# SHEET1.net
KiCad netlist of a schematic drawn in Altium Designer
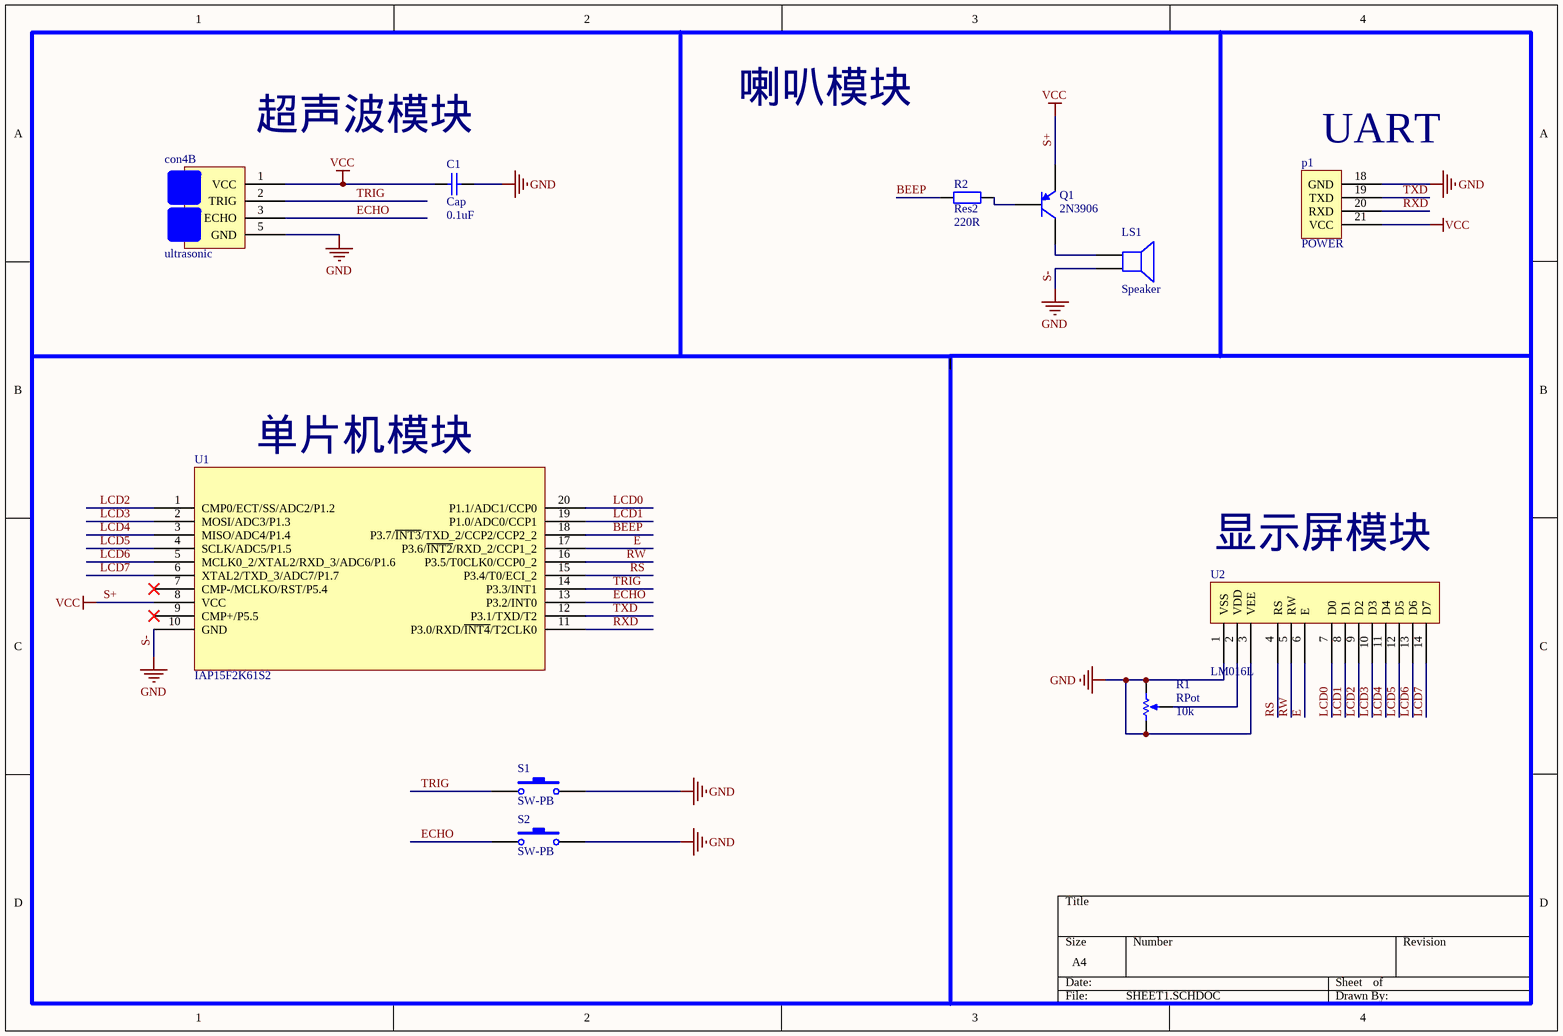
[diagram p0: SHEET1.SCHDOC]

(export (version "E")
  (design (tool "Eeschema 10.0.6"))
  (components
    (comp (ref "C1")
      (value "Cap")
      (footprint "LED")
      (description "Capacitor")
      (fields (field (name "ALTIUM_VALUE") "0.1uF") (field (name "PUBLISHER") "Altium Limited"))
      (libsource (lib "Miscellaneous Devices") (part "Cap"))
    )
    (comp (ref "con4")
      (value "ultrasonic")
      (footprint "sonic")
      (libsource (lib "Schlib1") (part "ultrasonic"))
    )
    (comp (ref "LS1")
      (value "Speaker")
      (footprint "SPEAKER")
      (description "Loudspeaker")
      (fields (field (name "PUBLISHER") "Altium Limited"))
      (libsource (lib "Miscellaneous Devices") (part "Speaker"))
    )
    (comp (ref "p1") (value "POWER") (footprint "POWER") (libsource (lib "Schlib1") (part "POWER")))
    (comp (ref "Q1")
      (value "2N3906")
      (footprint "TO-92A")
      (description "PNP General Purpose Amplifier")
      (fields (field (name "PUBLISHER") "Altium Limited"))
      (libsource (lib "Miscellaneous Devices") (part "2N3906"))
    )
    (comp (ref "R1")
      (value "RPot")
      (footprint "RESADJ")
      (description "Potentiometer")
      (fields (field (name "ALTIUM_VALUE") "10k") (field (name "PUBLISHER") "Altium Limited"))
      (libsource (lib "Miscellaneous Devices") (part "RPot"))
    )
    (comp (ref "R2")
      (value "Res2")
      (footprint "AXIAL-0.4")
      (description "Resistor")
      (fields (field (name "ALTIUM_VALUE") "220R") (field (name "PUBLISHER") "Altium Limited"))
      (libsource (lib "Miscellaneous Devices") (part "Res2"))
    )
    (comp (ref "S1")
      (value "SW-PB")
      (footprint "bottom")
      (description "Switch")
      (fields (field (name "PUBLISHER") "Altium Limited"))
      (libsource (lib "Miscellaneous Devices") (part "SW-PB"))
    )
    (comp (ref "S2")
      (value "SW-PB")
      (footprint "bottom")
      (description "Switch")
      (fields (field (name "PUBLISHER") "Altium Limited"))
      (libsource (lib "Miscellaneous Devices") (part "SW-PB"))
    )
    (comp (ref "U1")
      (value "IAP15F2K61S2")
      (footprint "DIP20")
      (libsource (lib "Schlib1") (part "IAP15F2K61S2"))
    )
    (comp (ref "U2") (value "LM016L") (footprint "LCD1602") (libsource (lib "Schlib1") (part "LM016L")))
  )
  (nets
    (net (code "1") (name "/BEEP") (class "Default")
      (node (ref "R2") (pin "1") (pinfunction "1_1") (pintype "passive"))
      (node (ref "U1") (pin "18") (pinfunction "P3.7/~{INT3}/TXD_2/CCP2/CCP2_2_18") (pintype "passive"))
    )
    (net (code "2") (name "/E") (class "Default")
      (node (ref "U1") (pin "17") (pinfunction "P3.6/~{INT2}/RXD_2/CCP1_2_17") (pintype "passive"))
      (node (ref "U2") (pin "6") (pinfunction "E_6") (pintype "passive"))
    )
    (net (code "3") (name "/ECHO") (class "Default")
      (node (ref "S2") (pin "1") (pinfunction "1_1") (pintype "passive"))
      (node (ref "U1") (pin "13") (pinfunction "P3.2/INT0_13") (pintype "passive"))
      (node (ref "con4") (pin "3") (pinfunction "ECHO_3") (pintype "passive"))
    )
    (net (code "4") (name "/LCD0") (class "Default")
      (node (ref "U1") (pin "20") (pinfunction "P1.1/ADC1/CCP0_20") (pintype "passive"))
      (node (ref "U2") (pin "7") (pinfunction "D0_7") (pintype "passive"))
    )
    (net (code "5") (name "/LCD1") (class "Default")
      (node (ref "U1") (pin "19") (pinfunction "P1.0/ADC0/CCP1_19") (pintype "passive"))
      (node (ref "U2") (pin "8") (pinfunction "D1_8") (pintype "passive"))
    )
    (net (code "6") (name "/LCD2") (class "Default")
      (node (ref "U1") (pin "1") (pinfunction "CMP0/ECT/SS/ADC2/P1.2_1") (pintype "passive"))
      (node (ref "U2") (pin "9") (pinfunction "D2_9") (pintype "passive"))
    )
    (net (code "7") (name "/LCD3") (class "Default")
      (node (ref "U1") (pin "2") (pinfunction "MOSI/ADC3/P1.3_2") (pintype "passive"))
      (node (ref "U2") (pin "10") (pinfunction "D3_10") (pintype "passive"))
    )
    (net (code "8") (name "/LCD4") (class "Default")
      (node (ref "U1") (pin "3") (pinfunction "MISO/ADC4/P1.4_3") (pintype "passive"))
      (node (ref "U2") (pin "11") (pinfunction "D4_11") (pintype "passive"))
    )
    (net (code "9") (name "/LCD5") (class "Default")
      (node (ref "U1") (pin "4") (pinfunction "SCLK/ADC5/P1.5_4") (pintype "passive"))
      (node (ref "U2") (pin "12") (pinfunction "D5_12") (pintype "passive"))
    )
    (net (code "10") (name "/LCD6") (class "Default")
      (node (ref "U1") (pin "5") (pinfunction "MCLK0_2/XTAL2/RXD_3/ADC6/P1.6_5") (pintype "passive"))
      (node (ref "U2") (pin "13") (pinfunction "D6_13") (pintype "passive"))
    )
    (net (code "11") (name "/LCD7") (class "Default")
      (node (ref "U1") (pin "6") (pinfunction "XTAL2/TXD_3/ADC7/P1.7_6") (pintype "passive"))
      (node (ref "U2") (pin "14") (pinfunction "D7_14") (pintype "passive"))
    )
    (net (code "12") (name "/RS") (class "Default")
      (node (ref "U1") (pin "15") (pinfunction "P3.4/T0/ECI_2_15") (pintype "passive"))
      (node (ref "U2") (pin "4") (pinfunction "RS_4") (pintype "passive"))
    )
    (net (code "13") (name "/RW") (class "Default")
      (node (ref "U1") (pin "16") (pinfunction "P3.5/T0CLK0/CCP0_2_16") (pintype "passive"))
      (node (ref "U2") (pin "5") (pinfunction "RW_5") (pintype "passive"))
    )
    (net (code "14") (name "/RXD") (class "Default")
      (node (ref "U1") (pin "11") (pinfunction "P3.0/RXD/~{INT4}/T2CLK0_11") (pintype "passive"))
      (node (ref "p1") (pin "20") (pinfunction "RXD_20") (pintype "passive"))
    )
    (net (code "15") (name "/TRIG") (class "Default")
      (node (ref "S1") (pin "1") (pinfunction "1_1") (pintype "passive"))
      (node (ref "U1") (pin "14") (pinfunction "P3.3/INT1_14") (pintype "passive"))
      (node (ref "con4") (pin "2") (pinfunction "TRIG_2") (pintype "passive"))
    )
    (net (code "16") (name "/TXD") (class "Default")
      (node (ref "U1") (pin "12") (pinfunction "P3.1/TXD/T2_12") (pintype "passive"))
      (node (ref "p1") (pin "19") (pinfunction "TXD_19") (pintype "passive"))
    )
    (net (code "17") (name "GND") (class "Default")
      (node (ref "C1") (pin "2") (pinfunction "2_2") (pintype "passive"))
      (node (ref "LS1") (pin "2") (pinfunction "2_2") (pintype "passive"))
      (node (ref "R1") (pin "1") (pinfunction "TOP_1") (pintype "passive"))
      (node (ref "R1") (pin "2") (pinfunction "BOT_2") (pintype "passive"))
      (node (ref "S1") (pin "2") (pinfunction "2_2") (pintype "passive"))
      (node (ref "S2") (pin "2") (pinfunction "2_2") (pintype "passive"))
      (node (ref "U1") (pin "10") (pinfunction "GND_10") (pintype "passive"))
      (node (ref "U2") (pin "1") (pinfunction "VSS_1") (pintype "passive"))
      (node (ref "U2") (pin "3") (pinfunction "VEE_3") (pintype "passive"))
      (node (ref "con4") (pin "5") (pinfunction "GND_5") (pintype "passive"))
      (node (ref "p1") (pin "18") (pinfunction "GND_18") (pintype "passive"))
    )
    (net (code "18") (name "Net-(Q1-B)") (class "Default")
      (node (ref "Q1") (pin "2") (pinfunction "B_2") (pintype "passive"))
      (node (ref "R2") (pin "2") (pinfunction "2_2") (pintype "passive"))
    )
    (net (code "19") (name "Net-(Q1-C)") (class "Default")
      (node (ref "LS1") (pin "1") (pinfunction "1_1") (pintype "passive"))
      (node (ref "Q1") (pin "3") (pinfunction "C_3") (pintype "passive"))
    )
    (net (code "20") (name "Net-(R1-TAP)") (class "Default")
      (node (ref "R1") (pin "3") (pinfunction "TAP_3") (pintype "passive"))
      (node (ref "U2") (pin "2") (pinfunction "VDD_2") (pintype "passive"))
    )
    (net (code "21") (name "VCC") (class "Default")
      (node (ref "C1") (pin "1") (pinfunction "1_1") (pintype "passive"))
      (node (ref "Q1") (pin "1") (pinfunction "E_1") (pintype "passive"))
      (node (ref "U1") (pin "8") (pinfunction "VCC_8") (pintype "passive"))
      (node (ref "con4") (pin "1") (pinfunction "VCC_1") (pintype "passive"))
      (node (ref "p1") (pin "21") (pinfunction "VCC_21") (pintype "passive"))
    )
    (net (code "22") (name "unconnected-(U1-CMP+{slash}P5.5-Pad9)") (class "Default")
      (node (ref "U1") (pin "9") (pinfunction "CMP+/P5.5_9") (pintype "passive+no_connect"))
    )
    (net (code "23") (name "unconnected-(U1-CMP-{slash}MCLKO{slash}RST{slash}P5.4-Pad7)") (class "Default")
      (node (ref "U1") (pin "7") (pinfunction "CMP-/MCLKO/RST/P5.4_7") (pintype "passive+no_connect"))
    )
  )
)
